# sumobot.net
KiCad netlist of a schematic drawn in EAGLE
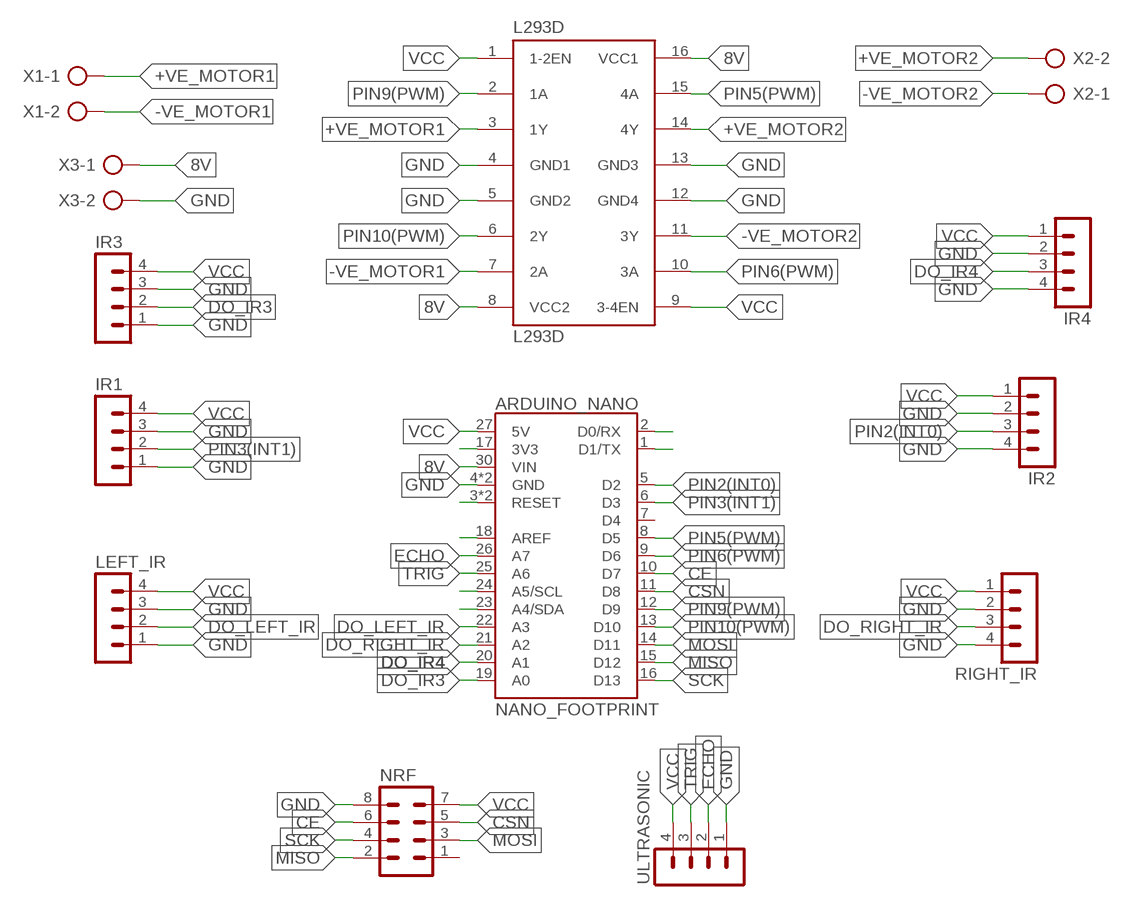
[diagram p0: schematic, sheet 1]

(export (version "E")
  (design (tool "Eeschema 10.0.6"))
  (components
    (comp (ref "ARDUINO_NANO")
      (value "NANO_FOOTPRINT")
      (footprint "eagle-import:NANO")
      (libsource (lib "eagle-import") (part "NANO_FOOTPRINT"))
    )
    (comp (ref "IR1")
      (value "MA04-1")
      (footprint "eagle-import:MA04-1")
      (libsource (lib "eagle-import") (part "MA04-1"))
    )
    (comp (ref "IR2")
      (value "MA04-1")
      (footprint "eagle-import:MA04-1")
      (libsource (lib "eagle-import") (part "MA04-1"))
    )
    (comp (ref "IR3")
      (value "MA04-1")
      (footprint "eagle-import:MA04-1")
      (libsource (lib "eagle-import") (part "MA04-1"))
    )
    (comp (ref "IR4")
      (value "MA04-1")
      (footprint "eagle-import:MA04-1")
      (libsource (lib "eagle-import") (part "MA04-1"))
    )
    (comp (ref "L293D")
      (value "L293D")
      (footprint "eagle-import:DIL16")
      (libsource (lib "eagle-import") (part "L293D"))
    )
    (comp (ref "LEFT_IR")
      (value "MA04-1")
      (footprint "eagle-import:MA04-1")
      (libsource (lib "eagle-import") (part "MA04-1"))
    )
    (comp (ref "NRF")
      (value "MA04-2")
      (footprint "eagle-import:MA04-2")
      (libsource (lib "eagle-import") (part "MA04-2"))
    )
    (comp (ref "RIGHT_IR")
      (value "MA04-1")
      (footprint "eagle-import:MA04-1")
      (libsource (lib "eagle-import") (part "MA04-1"))
    )
    (comp (ref "ULTRASONIC")
      (value "MA04-1")
      (footprint "eagle-import:MA04-1")
      (libsource (lib "eagle-import") (part "MA04-1"))
    )
    (comp (ref "X1")
      (value "AK500/2")
      (footprint "eagle-import:AK500_2")
      (libsource (lib "eagle-import") (part "AK500/2"))
    )
    (comp (ref "X2")
      (value "AK500/2")
      (footprint "eagle-import:AK500_2")
      (libsource (lib "eagle-import") (part "AK500/2"))
    )
    (comp (ref "X3")
      (value "AK500/2")
      (footprint "eagle-import:AK500_2")
      (libsource (lib "eagle-import") (part "AK500/2"))
    )
  )
  (nets
    (net (code "1") (name "+VE_MOTOR1") (class "Default")
      (node (ref "L293D") (pin "3") (pinfunction "1Y_3") (pintype "output"))
      (node (ref "X1") (pin "1") (pinfunction "KL_1") (pintype "passive"))
    )
    (net (code "2") (name "+VE_MOTOR2") (class "Default")
      (node (ref "L293D") (pin "14") (pinfunction "4Y_14") (pintype "output"))
      (node (ref "X2") (pin "2") (pinfunction "KL_2") (pintype "passive"))
    )
    (net (code "3") (name "-VE_MOTOR1") (class "Default")
      (node (ref "L293D") (pin "7") (pinfunction "2A_7") (pintype "input"))
      (node (ref "X1") (pin "2") (pinfunction "KL_2") (pintype "passive"))
    )
    (net (code "4") (name "-VE_MOTOR2") (class "Default")
      (node (ref "L293D") (pin "11") (pinfunction "3Y_11") (pintype "output"))
      (node (ref "X2") (pin "1") (pinfunction "KL_1") (pintype "passive"))
    )
    (net (code "5") (name "8V") (class "Default")
      (node (ref "ARDUINO_NANO") (pin "30") (pinfunction "VIN_30") (pintype "bidirectional"))
      (node (ref "L293D") (pin "16") (pinfunction "VCC1_16") (pintype "power_in"))
      (node (ref "L293D") (pin "8") (pinfunction "VCC2_8") (pintype "power_in"))
      (node (ref "X3") (pin "1") (pinfunction "KL_1") (pintype "passive"))
    )
    (net (code "6") (name "CE") (class "Default")
      (node (ref "ARDUINO_NANO") (pin "10") (pinfunction "D7_10") (pintype "bidirectional"))
      (node (ref "NRF") (pin "6") (pinfunction "6_6") (pintype "passive"))
    )
    (net (code "7") (name "CSN") (class "Default")
      (node (ref "ARDUINO_NANO") (pin "11") (pinfunction "D8_11") (pintype "bidirectional"))
      (node (ref "NRF") (pin "5") (pinfunction "5_5") (pintype "passive"))
    )
    (net (code "8") (name "DO_IR3") (class "Default")
      (node (ref "ARDUINO_NANO") (pin "19") (pinfunction "A0_19") (pintype "bidirectional"))
      (node (ref "IR3") (pin "2") (pinfunction "2_2") (pintype "passive"))
    )
    (net (code "9") (name "DO_IR4") (class "Default")
      (node (ref "ARDUINO_NANO") (pin "20") (pinfunction "A1_20") (pintype "bidirectional"))
      (node (ref "IR4") (pin "3") (pinfunction "3_3") (pintype "passive"))
    )
    (net (code "10") (name "DO_LEFT_IR") (class "Default")
      (node (ref "ARDUINO_NANO") (pin "22") (pinfunction "A3_22") (pintype "bidirectional"))
      (node (ref "LEFT_IR") (pin "2") (pinfunction "2_2") (pintype "passive"))
    )
    (net (code "11") (name "DO_RIGHT_IR") (class "Default")
      (node (ref "ARDUINO_NANO") (pin "21") (pinfunction "A2_21") (pintype "bidirectional"))
      (node (ref "RIGHT_IR") (pin "3") (pinfunction "3_3") (pintype "passive"))
    )
    (net (code "12") (name "ECHO") (class "Default")
      (node (ref "ARDUINO_NANO") (pin "26") (pinfunction "A7_26") (pintype "bidirectional"))
      (node (ref "ULTRASONIC") (pin "2") (pinfunction "2_2") (pintype "passive"))
    )
    (net (code "13") (name "GND") (class "Default")
      (node (ref "ARDUINO_NANO") (pin "29") (pinfunction "GND_29") (pintype "bidirectional"))
      (node (ref "ARDUINO_NANO") (pin "4") (pinfunction "GND_4") (pintype "bidirectional"))
      (node (ref "IR1") (pin "1") (pinfunction "1_1") (pintype "passive"))
      (node (ref "IR1") (pin "3") (pinfunction "3_3") (pintype "passive"))
      (node (ref "IR2") (pin "2") (pinfunction "2_2") (pintype "passive"))
      (node (ref "IR2") (pin "4") (pinfunction "4_4") (pintype "passive"))
      (node (ref "IR3") (pin "1") (pinfunction "1_1") (pintype "passive"))
      (node (ref "IR3") (pin "3") (pinfunction "3_3") (pintype "passive"))
      (node (ref "IR4") (pin "2") (pinfunction "2_2") (pintype "passive"))
      (node (ref "IR4") (pin "4") (pinfunction "4_4") (pintype "passive"))
      (node (ref "L293D") (pin "12") (pinfunction "GND4_12") (pintype "power_in"))
      (node (ref "L293D") (pin "13") (pinfunction "GND3_13") (pintype "power_in"))
      (node (ref "L293D") (pin "4") (pinfunction "GND1_4") (pintype "power_in"))
      (node (ref "L293D") (pin "5") (pinfunction "GND2_5") (pintype "power_in"))
      (node (ref "LEFT_IR") (pin "1") (pinfunction "1_1") (pintype "passive"))
      (node (ref "LEFT_IR") (pin "3") (pinfunction "3_3") (pintype "passive"))
      (node (ref "NRF") (pin "8") (pinfunction "8_8") (pintype "passive"))
      (node (ref "RIGHT_IR") (pin "2") (pinfunction "2_2") (pintype "passive"))
      (node (ref "RIGHT_IR") (pin "4") (pinfunction "4_4") (pintype "passive"))
      (node (ref "ULTRASONIC") (pin "1") (pinfunction "1_1") (pintype "passive"))
      (node (ref "X3") (pin "2") (pinfunction "KL_2") (pintype "passive"))
    )
    (net (code "14") (name "MISO") (class "Default")
      (node (ref "ARDUINO_NANO") (pin "15") (pinfunction "D12_15") (pintype "bidirectional"))
      (node (ref "NRF") (pin "2") (pinfunction "2_2") (pintype "passive"))
    )
    (net (code "15") (name "MOSI") (class "Default")
      (node (ref "ARDUINO_NANO") (pin "14") (pinfunction "D11_14") (pintype "bidirectional"))
      (node (ref "NRF") (pin "3") (pinfunction "3_3") (pintype "passive"))
    )
    (net (code "16") (name "Net-(ARDUINO_NANO-RESET-Pad28)") (class "Default")
      (node (ref "ARDUINO_NANO") (pin "28") (pinfunction "RESET_28") (pintype "bidirectional"))
      (node (ref "ARDUINO_NANO") (pin "3") (pinfunction "RESET_3") (pintype "bidirectional"))
    )
    (net (code "17") (name "PIN2(INT0)") (class "Default")
      (node (ref "ARDUINO_NANO") (pin "5") (pinfunction "D2_5") (pintype "bidirectional"))
      (node (ref "IR2") (pin "3") (pinfunction "3_3") (pintype "passive"))
    )
    (net (code "18") (name "PIN3(INT1)") (class "Default")
      (node (ref "ARDUINO_NANO") (pin "6") (pinfunction "D3_6") (pintype "bidirectional"))
      (node (ref "IR1") (pin "2") (pinfunction "2_2") (pintype "passive"))
    )
    (net (code "19") (name "PIN5(PWM)") (class "Default")
      (node (ref "ARDUINO_NANO") (pin "8") (pinfunction "D5_8") (pintype "bidirectional"))
      (node (ref "L293D") (pin "15") (pinfunction "4A_15") (pintype "input"))
    )
    (net (code "20") (name "PIN6(PWM)") (class "Default")
      (node (ref "ARDUINO_NANO") (pin "9") (pinfunction "D6_9") (pintype "bidirectional"))
      (node (ref "L293D") (pin "10") (pinfunction "3A_10") (pintype "input"))
    )
    (net (code "21") (name "PIN9(PWM)") (class "Default")
      (node (ref "ARDUINO_NANO") (pin "12") (pinfunction "D9_12") (pintype "bidirectional"))
      (node (ref "L293D") (pin "2") (pinfunction "1A_2") (pintype "input"))
    )
    (net (code "22") (name "PIN10(PWM)") (class "Default")
      (node (ref "ARDUINO_NANO") (pin "13") (pinfunction "D10_13") (pintype "bidirectional"))
      (node (ref "L293D") (pin "6") (pinfunction "2Y_6") (pintype "output"))
    )
    (net (code "23") (name "SCK") (class "Default")
      (node (ref "ARDUINO_NANO") (pin "16") (pinfunction "D13_16") (pintype "bidirectional"))
      (node (ref "NRF") (pin "4") (pinfunction "4_4") (pintype "passive"))
    )
    (net (code "24") (name "TRIG") (class "Default")
      (node (ref "ARDUINO_NANO") (pin "25") (pinfunction "A6_25") (pintype "bidirectional"))
      (node (ref "ULTRASONIC") (pin "3") (pinfunction "3_3") (pintype "passive"))
    )
    (net (code "25") (name "VCC") (class "Default")
      (node (ref "ARDUINO_NANO") (pin "27") (pinfunction "5V_27") (pintype "bidirectional"))
      (node (ref "IR1") (pin "4") (pinfunction "4_4") (pintype "passive"))
      (node (ref "IR2") (pin "1") (pinfunction "1_1") (pintype "passive"))
      (node (ref "IR3") (pin "4") (pinfunction "4_4") (pintype "passive"))
      (node (ref "IR4") (pin "1") (pinfunction "1_1") (pintype "passive"))
      (node (ref "L293D") (pin "1") (pinfunction "1-2EN_1") (pintype "input"))
      (node (ref "L293D") (pin "9") (pinfunction "3-4EN_9") (pintype "input"))
      (node (ref "LEFT_IR") (pin "4") (pinfunction "4_4") (pintype "passive"))
      (node (ref "NRF") (pin "7") (pinfunction "7_7") (pintype "passive"))
      (node (ref "RIGHT_IR") (pin "1") (pinfunction "1_1") (pintype "passive"))
      (node (ref "ULTRASONIC") (pin "4") (pinfunction "4_4") (pintype "passive"))
    )
    (net (code "26") (name "unconnected-(ARDUINO_NANO-3V3-Pad17)") (class "Default")
      (node (ref "ARDUINO_NANO") (pin "17") (pinfunction "3V3_17") (pintype "bidirectional"))
    )
    (net (code "27") (name "unconnected-(ARDUINO_NANO-A4{slash}SDA-Pad23)") (class "Default")
      (node (ref "ARDUINO_NANO") (pin "23") (pinfunction "A4/SDA_23") (pintype "bidirectional"))
    )
    (net (code "28") (name "unconnected-(ARDUINO_NANO-A5{slash}SCL-Pad24)") (class "Default")
      (node (ref "ARDUINO_NANO") (pin "24") (pinfunction "A5/SCL_24") (pintype "bidirectional"))
    )
    (net (code "29") (name "unconnected-(ARDUINO_NANO-AREF-Pad18)") (class "Default")
      (node (ref "ARDUINO_NANO") (pin "18") (pinfunction "AREF_18") (pintype "bidirectional"))
    )
    (net (code "30") (name "unconnected-(ARDUINO_NANO-D0{slash}RX-Pad2)") (class "Default")
      (node (ref "ARDUINO_NANO") (pin "2") (pinfunction "D0/RX_2") (pintype "bidirectional"))
    )
    (net (code "31") (name "unconnected-(ARDUINO_NANO-D1{slash}TX-Pad1)") (class "Default")
      (node (ref "ARDUINO_NANO") (pin "1") (pinfunction "D1/TX_1") (pintype "bidirectional"))
    )
    (net (code "32") (name "unconnected-(ARDUINO_NANO-D4-Pad7)") (class "Default")
      (node (ref "ARDUINO_NANO") (pin "7") (pinfunction "D4_7") (pintype "bidirectional"))
    )
    (net (code "33") (name "unconnected-(NRF-Pad1)") (class "Default")
      (node (ref "NRF") (pin "1") (pinfunction "1_1") (pintype "passive"))
    )
  )
)
